# v007_schematics.net
KiCad netlist of a schematic drawn in Altium Designer
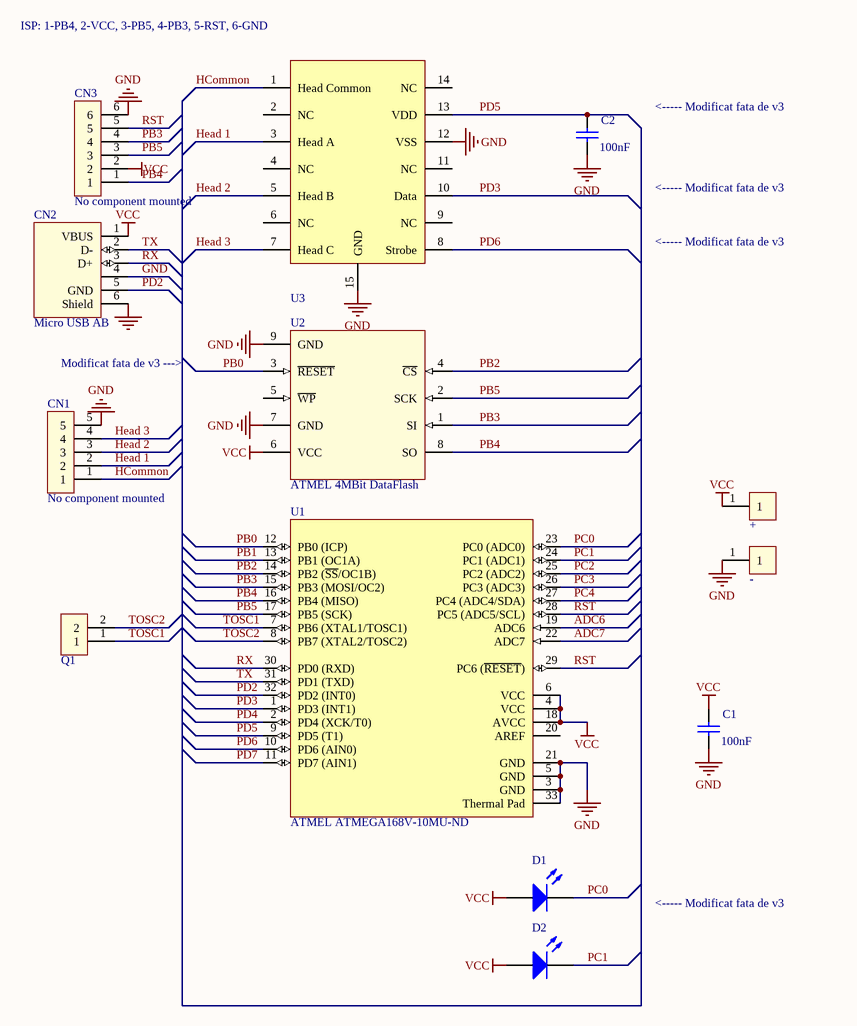
[diagram p0: v007 schematics.SCHDOC]

(export (version "E")
  (design (tool "Eeschema 10.0.6"))
  (components
    (comp (ref "+")
      (value "No component mounted")
      (footprint "SU01LS")
      (libsource (lib "*") (part "1pin smd"))
    )
    (comp (ref "-")
      (value "No component mounted")
      (footprint "SU01LS")
      (libsource (lib "*") (part "1pin smd"))
    )
    (comp (ref "C1")
      (value "100nF")
      (footprint "CC0603(0201)")
      (description "100nf Capacitor - Footprint CC0603 (0201)")
      (fields (field (name "PUBLISHER") "Altium Limited"))
      (libsource (lib "Miscellaneous Devices") (part "Cap"))
    )
    (comp (ref "C2")
      (value "100nF")
      (footprint "CC0603(0201)")
      (description "100nf Capacitor - Footprint CC0603 (0201)")
      (fields (field (name "PUBLISHER") "Altium Limited"))
      (libsource (lib "Miscellaneous Devices") (part "Cap"))
    )
    (comp (ref "CN1")
      (value "No component mounted")
      (footprint "SU05LSR")
      (libsource (lib "v4lib") (part "5pin smd"))
    )
    (comp (ref "CN2")
      (value "Micro USB AB")
      (footprint "Micro USB Receptacle small")
      (description "Connector Receptacle Micro USB AB SMD Reverse Angle")
      (fields
        (field (name "DIGI-KEY PART NUMBER") "H11635CT-ND")
        (field (name "MANUFACTURER") "Hirose Electric")
      )
      (libsource (lib "v4lib") (part "micro usb"))
    )
    (comp (ref "CN3")
      (value "No component mounted")
      (footprint "SU06LST thicker")
      (libsource (lib "v4lib") (part "6pin smd"))
    )
    (comp (ref "D1")
      (value "LED1")
      (footprint "CC1005(0402)")
      (description "LED 0402 GREEN 465NM TRANSPARENT")
      (fields
        (field (name "DIGI-KEY PART NUMBER") "511-1615-1-ND")
        (field (name "MANUFACTURER") "Rohm Semiconductor")
        (field (name "PUBLISHER") "Altium Limited")
      )
      (libsource (lib "Miscellaneous Devices") (part "LED3"))
    )
    (comp (ref "D2")
      (value "LED1")
      (footprint "CC1005(0402)")
      (description "LED 0402 RED 465NM TRANSPARENT")
      (fields
        (field (name "DIGI-KEY PART NUMBER") "511-1615-1-ND")
        (field (name "MANUFACTURER") "Rohm Semiconductor")
        (field (name "PUBLISHER") "Altium Limited")
      )
      (libsource (lib "Miscellaneous Devices") (part "LED3"))
    )
    (comp (ref "Q1")
      (value "32.768khz crystal 1.5 x 3.2mm")
      (footprint "Quartz SMD 2")
      (description "CRYSTAL 32.768KHZ 1.5 x 3.2mm")
      (fields
        (field (name "DIGI-KEY PART NUMBER") "535-9542-1-ND")
        (field (name "MANUFACTURER") "Abracon Corporation")
      )
      (libsource (lib "v4lib") (part "2pin smd"))
    )
    (comp (ref "U1")
      (value "ATMEL ATMEGA168V-10MU-ND")
      (footprint "32M1-A L 3")
      (description "IC AVR MCU 16K 10MHZ 32-QFN 8-Bit AVR Microcontroller")
      (fields
        (field (name "DIGI-KEY PART NUMBER") "ATMEGA168V-10MU-ND")
        (field (name "MANUFACTURER") "ATMEL")
        (field (name "PUBLISHER") "Altium Limited")
      )
      (libsource (lib "Atmel Microcontroller 8-Bit AVR") (part "ATmega8L-8MC"))
    )
    (comp (ref "U2")
      (value "ATMEL 4MBit DataFlash")
      (footprint "8m1-a mlf 3")
      (libsource (lib "v4lib") (part "at45db041b"))
    )
    (comp (ref "U3")
      (value "Asic 3V MLF14")
      (footprint "delta asic - 5")
      (fields (field (name "MANUFACTURER") "Magtek") (field (name "MANUFACTURER PART NUMBER") "21006540"))
      (libsource (lib "v4lib") (part "delta asic 3volt"))
    )
  )
  (nets
    (net (code "1") (name "/ADC6") (class "Default")
      (node (ref "U1") (pin "19") (pinfunction "ADC6_19") (pintype "input"))
    )
    (net (code "2") (name "/ADC7") (class "Default")
      (node (ref "U1") (pin "22") (pinfunction "ADC7_22") (pintype "input"))
    )
    (net (code "3") (name "/HCommon") (class "Default")
      (node (ref "CN1") (pin "1") (pinfunction "1_1") (pintype "passive"))
      (node (ref "U3") (pin "1") (pinfunction "Head_Common_1") (pintype "passive"))
    )
    (net (code "4") (name "/Head 1") (class "Default")
      (node (ref "CN1") (pin "2") (pinfunction "2_2") (pintype "passive"))
      (node (ref "U3") (pin "3") (pinfunction "Head_A_3") (pintype "passive"))
    )
    (net (code "5") (name "/Head 2") (class "Default")
      (node (ref "CN1") (pin "3") (pinfunction "3_3") (pintype "passive"))
      (node (ref "U3") (pin "5") (pinfunction "Head_B_5") (pintype "passive"))
    )
    (net (code "6") (name "/Head 3") (class "Default")
      (node (ref "CN1") (pin "4") (pinfunction "4_4") (pintype "passive"))
      (node (ref "U3") (pin "7") (pinfunction "Head_C_7") (pintype "passive"))
    )
    (net (code "7") (name "/PB0") (class "Default")
      (node (ref "U1") (pin "12") (pinfunction "PB0_(ICP)_12") (pintype "bidirectional"))
      (node (ref "U2") (pin "3") (pinfunction "~{RESET}_3") (pintype "input"))
    )
    (net (code "8") (name "/PB1") (class "Default")
      (node (ref "U1") (pin "13") (pinfunction "PB1_(OC1A)_13") (pintype "bidirectional"))
    )
    (net (code "9") (name "/PB2") (class "Default")
      (node (ref "U1") (pin "14") (pinfunction "PB2_(~{SS}/OC1B)_14") (pintype "bidirectional"))
      (node (ref "U2") (pin "4") (pinfunction "~{CS}_4") (pintype "input"))
    )
    (net (code "10") (name "/PB3") (class "Default")
      (node (ref "CN3") (pin "4") (pinfunction "4_4") (pintype "passive"))
      (node (ref "U1") (pin "15") (pinfunction "PB3_(MOSI/OC2)_15") (pintype "bidirectional"))
      (node (ref "U2") (pin "1") (pinfunction "SI_1") (pintype "input"))
    )
    (net (code "11") (name "/PB4") (class "Default")
      (node (ref "CN3") (pin "1") (pinfunction "1_1") (pintype "passive"))
      (node (ref "U1") (pin "16") (pinfunction "PB4_(MISO)_16") (pintype "bidirectional"))
      (node (ref "U2") (pin "8") (pinfunction "SO_8") (pintype "passive"))
    )
    (net (code "12") (name "/PB5") (class "Default")
      (node (ref "CN3") (pin "3") (pinfunction "3_3") (pintype "passive"))
      (node (ref "U1") (pin "17") (pinfunction "PB5_(SCK)_17") (pintype "bidirectional"))
      (node (ref "U2") (pin "2") (pinfunction "SCK_2") (pintype "input"))
    )
    (net (code "13") (name "/PC0") (class "Default")
      (node (ref "D1") (pin "2") (pinfunction "K_2") (pintype "passive"))
      (node (ref "U1") (pin "23") (pinfunction "PC0_(ADC0)_23") (pintype "bidirectional"))
    )
    (net (code "14") (name "/PC1") (class "Default")
      (node (ref "D2") (pin "2") (pinfunction "K_2") (pintype "passive"))
      (node (ref "U1") (pin "24") (pinfunction "PC1_(ADC1)_24") (pintype "bidirectional"))
    )
    (net (code "15") (name "/PC2") (class "Default")
      (node (ref "U1") (pin "25") (pinfunction "PC2_(ADC2)_25") (pintype "bidirectional"))
    )
    (net (code "16") (name "/PC3") (class "Default")
      (node (ref "U1") (pin "26") (pinfunction "PC3_(ADC3)_26") (pintype "bidirectional"))
    )
    (net (code "17") (name "/PC4") (class "Default")
      (node (ref "U1") (pin "27") (pinfunction "PC4_(ADC4/SDA)_27") (pintype "bidirectional"))
    )
    (net (code "18") (name "/PD2") (class "Default")
      (node (ref "CN2") (pin "5") (pinfunction "GND_5") (pintype "passive"))
      (node (ref "U1") (pin "32") (pinfunction "PD2_(INT0)_32") (pintype "bidirectional"))
    )
    (net (code "19") (name "/PD3") (class "Default")
      (node (ref "U1") (pin "1") (pinfunction "PD3_(INT1)_1") (pintype "bidirectional"))
      (node (ref "U3") (pin "10") (pinfunction "Data_10") (pintype "passive"))
    )
    (net (code "20") (name "/PD4") (class "Default")
      (node (ref "U1") (pin "2") (pinfunction "PD4_(XCK/T0)_2") (pintype "bidirectional"))
    )
    (net (code "21") (name "/PD5") (class "Default")
      (node (ref "C2") (pin "1") (pinfunction "1_1") (pintype "passive"))
      (node (ref "U1") (pin "9") (pinfunction "PD5_(T1)_9") (pintype "bidirectional"))
      (node (ref "U3") (pin "13") (pinfunction "VDD_13") (pintype "passive"))
    )
    (net (code "22") (name "/PD6") (class "Default")
      (node (ref "U1") (pin "10") (pinfunction "PD6_(AIN0)_10") (pintype "bidirectional"))
      (node (ref "U3") (pin "8") (pinfunction "Strobe_8") (pintype "passive"))
    )
    (net (code "23") (name "/PD7") (class "Default")
      (node (ref "U1") (pin "11") (pinfunction "PD7_(AIN1)_11") (pintype "bidirectional"))
    )
    (net (code "24") (name "/RST") (class "Default")
      (node (ref "CN3") (pin "5") (pinfunction "5_5") (pintype "passive"))
      (node (ref "U1") (pin "28") (pinfunction "PC5_(ADC5/SCL)_28") (pintype "bidirectional"))
      (node (ref "U1") (pin "29") (pinfunction "PC6_(~{RESET})_29") (pintype "bidirectional"))
    )
    (net (code "25") (name "/RX") (class "Default")
      (node (ref "CN2") (pin "3") (pinfunction "D+_3") (pintype "bidirectional"))
      (node (ref "U1") (pin "30") (pinfunction "PD0_(RXD)_30") (pintype "bidirectional"))
    )
    (net (code "26") (name "/TOSC1") (class "Default")
      (node (ref "Q1") (pin "1") (pinfunction "1_1") (pintype "passive"))
      (node (ref "U1") (pin "7") (pinfunction "PB6_(XTAL1/TOSC1)_7") (pintype "bidirectional"))
    )
    (net (code "27") (name "/TOSC2") (class "Default")
      (node (ref "Q1") (pin "2") (pinfunction "2_2") (pintype "passive"))
      (node (ref "U1") (pin "8") (pinfunction "PB7_(XTAL2/TOSC2)_8") (pintype "bidirectional"))
    )
    (net (code "28") (name "/TX") (class "Default")
      (node (ref "CN2") (pin "2") (pinfunction "D-_2") (pintype "bidirectional"))
      (node (ref "U1") (pin "31") (pinfunction "PD1_(TXD)_31") (pintype "bidirectional"))
    )
    (net (code "29") (name "GND") (class "Default")
      (node (ref "-") (pin "1") (pinfunction "1_1") (pintype "passive"))
      (node (ref "C1") (pin "2") (pinfunction "2_2") (pintype "passive"))
      (node (ref "C2") (pin "2") (pinfunction "2_2") (pintype "passive"))
      (node (ref "CN1") (pin "5") (pinfunction "5_5") (pintype "passive"))
      (node (ref "CN2") (pin "4") (pintype "passive"))
      (node (ref "CN2") (pin "6") (pinfunction "Shield_6") (pintype "passive"))
      (node (ref "CN3") (pin "6") (pinfunction "6_6") (pintype "passive"))
      (node (ref "U1") (pin "21") (pinfunction "GND_21") (pintype "power_in"))
      (node (ref "U1") (pin "3") (pinfunction "GND_3") (pintype "power_in"))
      (node (ref "U1") (pin "33") (pinfunction "Thermal_Pad_33") (pintype "power_in"))
      (node (ref "U1") (pin "5") (pinfunction "GND_5") (pintype "power_in"))
      (node (ref "U2") (pin "7") (pinfunction "GND_7") (pintype "passive"))
      (node (ref "U2") (pin "9") (pinfunction "GND_9") (pintype "passive"))
      (node (ref "U3") (pin "12") (pinfunction "VSS_12") (pintype "passive"))
      (node (ref "U3") (pin "15") (pinfunction "GND_15") (pintype "passive"))
    )
    (net (code "30") (name "VCC") (class "Default")
      (node (ref "+") (pin "1") (pinfunction "1_1") (pintype "passive"))
      (node (ref "C1") (pin "1") (pinfunction "1_1") (pintype "passive"))
      (node (ref "CN2") (pin "1") (pinfunction "VBUS_1") (pintype "power_in"))
      (node (ref "CN3") (pin "2") (pinfunction "2_2") (pintype "passive"))
      (node (ref "D1") (pin "1") (pinfunction "A_1") (pintype "passive"))
      (node (ref "D2") (pin "1") (pinfunction "A_1") (pintype "passive"))
      (node (ref "U1") (pin "18") (pinfunction "AVCC_18") (pintype "power_in"))
      (node (ref "U1") (pin "4") (pinfunction "VCC_4") (pintype "power_in"))
      (node (ref "U1") (pin "6") (pinfunction "VCC_6") (pintype "power_in"))
      (node (ref "U2") (pin "6") (pinfunction "VCC_6") (pintype "power_in"))
    )
    (net (code "31") (name "unconnected-(U1-AREF-Pad20)") (class "Default")
      (node (ref "U1") (pin "20") (pinfunction "AREF_20") (pintype "passive"))
    )
    (net (code "32") (name "unconnected-(U2-~{WP}-Pad5)") (class "Default")
      (node (ref "U2") (pin "5") (pinfunction "~{WP}_5") (pintype "input"))
    )
    (net (code "33") (name "unconnected-(U3-NC-Pad2)") (class "Default")
      (node (ref "U3") (pin "2") (pinfunction "NC_2") (pintype "passive"))
    )
    (net (code "34") (name "unconnected-(U3-NC-Pad4)") (class "Default")
      (node (ref "U3") (pin "4") (pinfunction "NC_4") (pintype "passive"))
    )
    (net (code "35") (name "unconnected-(U3-NC-Pad6)") (class "Default")
      (node (ref "U3") (pin "6") (pinfunction "NC_6") (pintype "passive"))
    )
    (net (code "36") (name "unconnected-(U3-NC-Pad9)") (class "Default")
      (node (ref "U3") (pin "9") (pinfunction "NC_9") (pintype "passive"))
    )
    (net (code "37") (name "unconnected-(U3-NC-Pad11)") (class "Default")
      (node (ref "U3") (pin "11") (pinfunction "NC_11") (pintype "passive"))
    )
    (net (code "38") (name "unconnected-(U3-NC-Pad14)") (class "Default")
      (node (ref "U3") (pin "14") (pinfunction "NC_14") (pintype "passive"))
    )
  )
)
